# spindle-driver.net
KiCad netlist of a schematic drawn in EAGLE
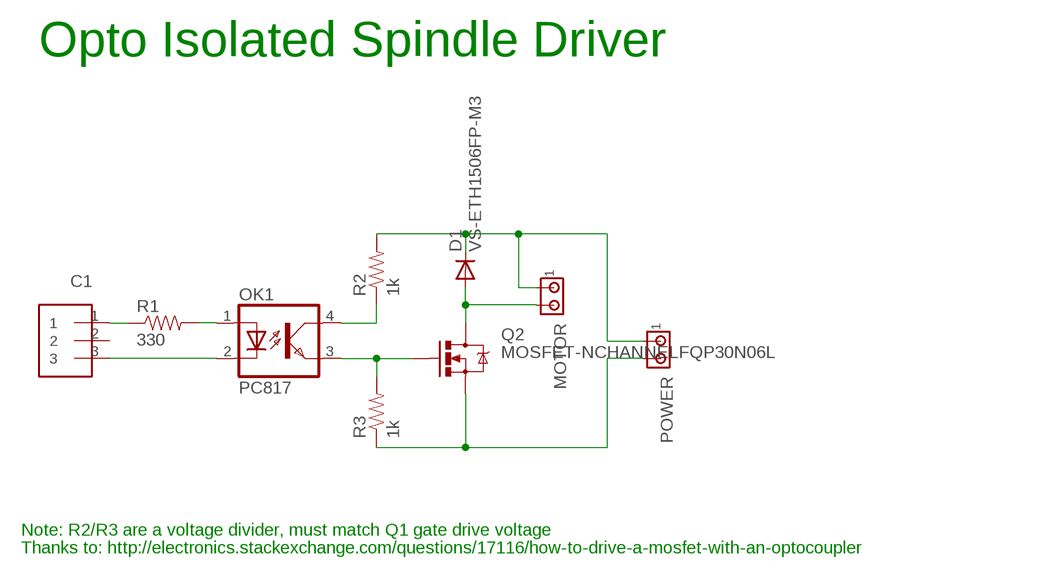
[diagram p0: schematic, sheet 1]

(export (version "E")
  (design (tool "Eeschema 10.0.6"))
  (components
    (comp (ref "C1")
      (value "CONN-3XH-3")
      (footprint "eagle-import:XH-3")
      (libsource (lib "eagle-import") (part "CONN-3XH-3"))
    )
    (comp (ref "D1")
      (value "VS-ETH1506FP-M3")
      (footprint "eagle-import:SMB")
      (libsource (lib "eagle-import") (part "DIODE-SMB"))
    )
    (comp (ref "MOTOR")
      (value "MTA02-156")
      (footprint "eagle-import:1X2MTA")
      (libsource (lib "eagle-import") (part "MTA02-156"))
    )
    (comp (ref "OK1")
      (value "PC817")
      (footprint "eagle-import:DIL04")
      (fields (field (name "MPN") "PC817X4J000F"))
      (libsource (lib "eagle-import") (part "PC817"))
    )
    (comp (ref "POWER")
      (value "MTA02-156")
      (footprint "eagle-import:1X2MTA")
      (libsource (lib "eagle-import") (part "MTA02-156"))
    )
    (comp (ref "Q2")
      (value "MOSFET-NCHANNELFQP30N06L")
      (footprint "eagle-import:TO220V")
      (libsource (lib "eagle-import") (part "MOSFET-NCHANNELFQP30N06L"))
    )
    (comp (ref "R1")
      (value "330")
      (footprint "eagle-import:0805-RC")
      (libsource (lib "eagle-import") (part "RESISTOR0805"))
    )
    (comp (ref "R2")
      (value "1k")
      (footprint "eagle-import:0805-RC")
      (libsource (lib "eagle-import") (part "RESISTOR0805"))
    )
    (comp (ref "R3")
      (value "1k")
      (footprint "eagle-import:0805-RC")
      (libsource (lib "eagle-import") (part "RESISTOR0805"))
    )
  )
  (nets
    (net (code "1") (name "Net-(C1-Pad1)") (class "Default")
      (node (ref "C1") (pin "1") (pinfunction "1_1") (pintype "bidirectional"))
      (node (ref "R1") (pin "1") (pinfunction "1_1") (pintype "passive"))
    )
    (net (code "2") (name "Net-(D1-PadC)") (class "Default")
      (node (ref "D1") (pin "C") (pinfunction "C_C") (pintype "passive"))
      (node (ref "MOTOR") (pin "1") (pinfunction "1_1") (pintype "passive"))
      (node (ref "POWER") (pin "1") (pinfunction "1_1") (pintype "passive"))
      (node (ref "R2") (pin "2") (pinfunction "2_2") (pintype "passive"))
    )
    (net (code "3") (name "Net-(OK1-A)") (class "Default")
      (node (ref "OK1") (pin "1") (pinfunction "A_1") (pintype "passive"))
      (node (ref "R1") (pin "2") (pinfunction "2_2") (pintype "passive"))
    )
    (net (code "4") (name "Net-(OK1-C)") (class "Default")
      (node (ref "C1") (pin "3") (pinfunction "3_3") (pintype "bidirectional"))
      (node (ref "OK1") (pin "2") (pinfunction "C_2") (pintype "passive"))
    )
    (net (code "5") (name "Net-(OK1-COL)") (class "Default")
      (node (ref "OK1") (pin "4") (pinfunction "COL_4") (pintype "passive"))
      (node (ref "R2") (pin "1") (pinfunction "1_1") (pintype "passive"))
    )
    (net (code "6") (name "Net-(OK1-EMIT)") (class "Default")
      (node (ref "OK1") (pin "3") (pinfunction "EMIT_3") (pintype "passive"))
      (node (ref "Q2") (pin "1") (pinfunction "G_1") (pintype "passive"))
      (node (ref "R3") (pin "2") (pinfunction "2_2") (pintype "passive"))
    )
    (net (code "7") (name "Net-(Q2-D)") (class "Default")
      (node (ref "D1") (pin "A") (pinfunction "A_A") (pintype "passive"))
      (node (ref "MOTOR") (pin "2") (pinfunction "2_2") (pintype "passive"))
      (node (ref "Q2") (pin "2") (pinfunction "D_2") (pintype "passive"))
    )
    (net (code "8") (name "Net-(Q2-S)") (class "Default")
      (node (ref "POWER") (pin "2") (pinfunction "2_2") (pintype "passive"))
      (node (ref "Q2") (pin "3") (pinfunction "S_3") (pintype "passive"))
      (node (ref "R3") (pin "1") (pinfunction "1_1") (pintype "passive"))
    )
    (net (code "9") (name "unconnected-(C1-Pad2)") (class "Default")
      (node (ref "C1") (pin "2") (pinfunction "2_2") (pintype "bidirectional"))
    )
  )
)
